# Sheet2.net
KiCad netlist of a schematic drawn in Altium Designer
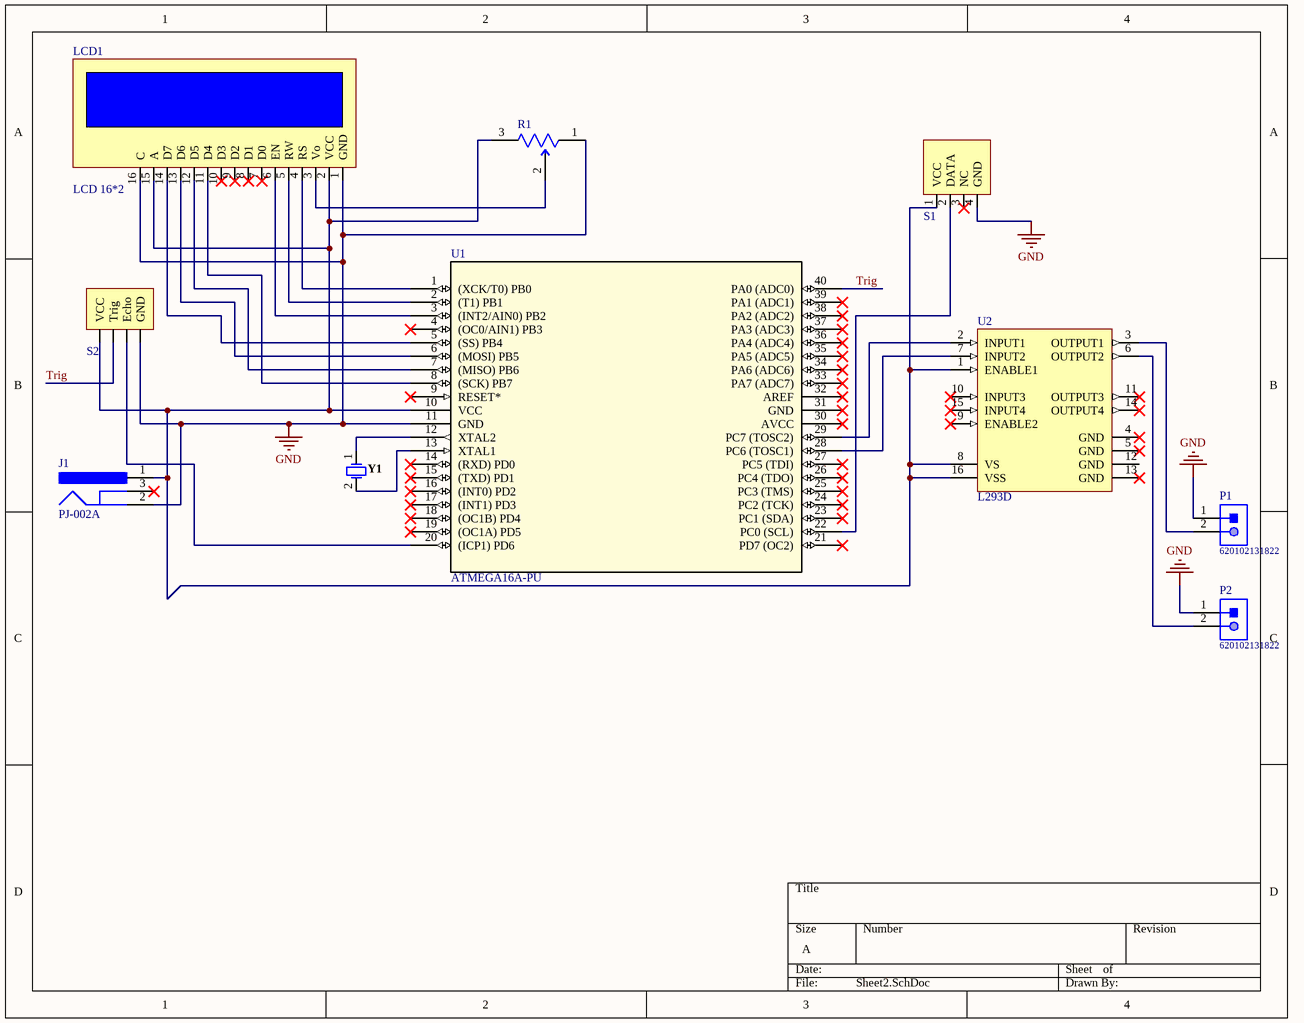
[diagram p0: Sheet2.SchDoc]

(export (version "E")
  (design (tool "Eeschema 10.0.6"))
  (components
    (comp (ref "J1")
      (value "PJ-002A")
      (footprint "CUI-PJ-002A_V")
      (fields (field (name "MANUFACTURER") "CUIInc.") (field (name "MANUFACTURER_1") "CUI"))
      (libsource (lib "AVRpr") (part "CMP-2000-06895-2"))
    )
    (comp (ref "LCD1") (value "LCD 16*2") (footprint "LCD1602") (libsource (lib "AVRpr") (part "LCD 16*2")))
    (comp (ref "P1")
      (value "620102131822")
      (footprint "620102131822")
      (description "Male Shrouded Header WR-WTB, SMT, Right Angled, pitch 2 mm, 1 x 2 position")
      (fields
        (field (name "MANUFACTURER") "Wurth Elektronik")
        (field (name "MANUFACTURER_1") "Wurth Electronics")
        (field (name "PUBLISHER") "WurthElektronik")
      )
      (libsource (lib "AVRpr") (part "CMP-1502-00669-1"))
    )
    (comp (ref "P2")
      (value "620102131822")
      (footprint "620102131822")
      (description "Male Shrouded Header WR-WTB, SMT, Right Angled, pitch 2 mm, 1 x 2 position")
      (fields
        (field (name "MANUFACTURER") "Wurth Elektronik")
        (field (name "MANUFACTURER_1") "Wurth Electronics")
        (field (name "PUBLISHER") "WurthElektronik")
      )
      (libsource (lib "AVRpr") (part "CMP-1502-00669-1"))
    )
    (comp (ref "R1")
      (value "3006P-1-103LF")
      (footprint "FP-3006P-MFG")
      (description "TRIMMER 10KOHM 0.75W PC PIN SIDE")
      (fields (field (name "TOLERANCE") "10%") (field (name "MANUFACTURER") "Bourns"))
      (libsource (lib "AVRpr") (part "CMP-07234-000047-1"))
    )
    (comp (ref "S1")
      (value "386")
      (footprint "DHT11")
      (description "SENSOR HUMID/TEMP 5V DTL 5% MOD")
      (fields (field (name "MANUFACTURER") "Adafruit Industries"))
      (libsource (lib "AVRpr") (part "386"))
    )
    (comp (ref "S2")
      (value "HC-SR04")
      (footprint "HC-SR04")
      (description "Ultrasonic Sensor Module, Rectangular, 20-4000 mm, 5 V, 15 mA, Arduino Compatible")
      (fields (field (name "MANUFACTURER") "OSEPP"))
      (libsource (lib "AVRpr") (part "HC-SR04"))
    )
    (comp (ref "U1")
      (value "ATMEGA16A-PU")
      (footprint "ATmega16A")
      (description "8-bit AVR MCU, 16 KB, 1024 Bytes, 16 MHz, 2.7 to 5.5V, PDIP-40, RoHS")
      (fields (field (name "MANUFACTURER") "Microchip / Atmel"))
      (libsource (lib "AVRpr") (part "ATMEGA16A-PU"))
    )
    (comp (ref "U2")
      (value "L293D")
      (footprint "STM-L293D-16")
      (description "Push-Pull Four Channel Driver with Diode, 4.5 to 36 V, -40 to 150 degC, 16-Pin PDIP, RoHS, Tube")
      (fields (field (name "MANUFACTURER") "STMicroelectronics"))
      (libsource (lib "AVRpr") (part "L293D"))
    )
    (comp (ref "Y1")
      (value "FOXSLF/080-20")
      (footprint "FOX-FOXSLF080-20")
      (description "Resistance Weld Thru-Hole Crystal, 8 MHz, -20 to 70 degC, 2-Pin THD, RoHS, Bulk")
      (fields (field (name "MANUFACTURER") "Fox Electronics"))
      (libsource (lib "AVRpr") (part "CMP-1749-00002-1"))
    )
  )
  (nets
    (net (code "1") (name "/Trig") (class "Default")
      (node (ref "S2") (pin "2") (pinfunction "Trig_2") (pintype "passive"))
      (node (ref "U1") (pin "40") (pinfunction "PA0_(ADC0)_40") (pintype "bidirectional"))
    )
    (net (code "2") (name "GND") (class "Default")
      (node (ref "J1") (pin "2") (pinfunction "2_2") (pintype "passive"))
      (node (ref "LCD1") (pin "1") (pinfunction "GND_1") (pintype "passive"))
      (node (ref "LCD1") (pin "16") (pinfunction "C_16") (pintype "passive"))
      (node (ref "P1") (pin "1") (pinfunction "1_1") (pintype "passive"))
      (node (ref "P2") (pin "1") (pinfunction "1_1") (pintype "passive"))
      (node (ref "R1") (pin "1") (pinfunction "CCW_1") (pintype "passive"))
      (node (ref "S1") (pin "4") (pinfunction "GND_4") (pintype "passive"))
      (node (ref "S2") (pin "4") (pinfunction "GND_4") (pintype "passive"))
      (node (ref "U1") (pin "11") (pinfunction "GND_11") (pintype "power_in"))
    )
    (net (code "3") (name "Net-(LCD1-A)") (class "Default")
      (node (ref "J1") (pin "1") (pinfunction "1_1") (pintype "passive"))
      (node (ref "LCD1") (pin "15") (pinfunction "A_15") (pintype "passive"))
      (node (ref "LCD1") (pin "2") (pinfunction "VCC_2") (pintype "passive"))
      (node (ref "R1") (pin "3") (pinfunction "CW_3") (pintype "passive"))
      (node (ref "S1") (pin "1") (pinfunction "VCC_1") (pintype "passive"))
      (node (ref "S2") (pin "1") (pinfunction "VCC_1") (pintype "passive"))
      (node (ref "U1") (pin "10") (pinfunction "VCC_10") (pintype "power_in"))
      (node (ref "U2") (pin "1") (pinfunction "ENABLE1_1") (pintype "input"))
      (node (ref "U2") (pin "16") (pinfunction "VSS_16") (pintype "power_in"))
      (node (ref "U2") (pin "8") (pinfunction "VS_8") (pintype "power_in"))
    )
    (net (code "4") (name "Net-(LCD1-D4)") (class "Default")
      (node (ref "LCD1") (pin "11") (pinfunction "D4_11") (pintype "passive"))
      (node (ref "U1") (pin "8") (pinfunction "(SCK)_PB7_8") (pintype "bidirectional"))
    )
    (net (code "5") (name "Net-(LCD1-D5)") (class "Default")
      (node (ref "LCD1") (pin "12") (pinfunction "D5_12") (pintype "passive"))
      (node (ref "U1") (pin "7") (pinfunction "(MISO)_PB6_7") (pintype "bidirectional"))
    )
    (net (code "6") (name "Net-(LCD1-D6)") (class "Default")
      (node (ref "LCD1") (pin "13") (pinfunction "D6_13") (pintype "passive"))
      (node (ref "U1") (pin "6") (pinfunction "(MOSI)_PB5_6") (pintype "bidirectional"))
    )
    (net (code "7") (name "Net-(LCD1-D7)") (class "Default")
      (node (ref "LCD1") (pin "14") (pinfunction "D7_14") (pintype "passive"))
      (node (ref "U1") (pin "5") (pinfunction "(SS)_PB4_5") (pintype "bidirectional"))
    )
    (net (code "8") (name "Net-(LCD1-EN)") (class "Default")
      (node (ref "LCD1") (pin "6") (pinfunction "EN_6") (pintype "passive"))
      (node (ref "U1") (pin "3") (pinfunction "(INT2/AIN0)_PB2_3") (pintype "bidirectional"))
    )
    (net (code "9") (name "Net-(LCD1-RS)") (class "Default")
      (node (ref "LCD1") (pin "4") (pinfunction "RS_4") (pintype "passive"))
      (node (ref "U1") (pin "1") (pinfunction "(XCK/T0)_PB0_1") (pintype "bidirectional"))
    )
    (net (code "10") (name "Net-(LCD1-RW)") (class "Default")
      (node (ref "LCD1") (pin "5") (pinfunction "RW_5") (pintype "passive"))
      (node (ref "U1") (pin "2") (pinfunction "(T1)_PB1_2") (pintype "bidirectional"))
    )
    (net (code "11") (name "Net-(LCD1-Vo)") (class "Default")
      (node (ref "LCD1") (pin "3") (pinfunction "Vo_3") (pintype "passive"))
      (node (ref "R1") (pin "2") (pinfunction "WIPER_2") (pintype "passive"))
    )
    (net (code "12") (name "Net-(S1-DATA)") (class "Default")
      (node (ref "S1") (pin "2") (pinfunction "DATA_2") (pintype "passive"))
      (node (ref "U1") (pin "22") (pinfunction "PC0_(SCL)_22") (pintype "bidirectional"))
    )
    (net (code "13") (name "Net-(S2-Echo)") (class "Default")
      (node (ref "S2") (pin "3") (pinfunction "Echo_3") (pintype "passive"))
      (node (ref "U1") (pin "20") (pinfunction "(ICP1)_PD6_20") (pintype "bidirectional"))
    )
    (net (code "14") (name "Net-(U1-PC6_(TOSC1))") (class "Default")
      (node (ref "U1") (pin "28") (pinfunction "PC6_(TOSC1)_28") (pintype "bidirectional"))
      (node (ref "U2") (pin "7") (pinfunction "INPUT2_7") (pintype "input"))
    )
    (net (code "15") (name "Net-(U1-PC7_(TOSC2))") (class "Default")
      (node (ref "U1") (pin "29") (pinfunction "PC7_(TOSC2)_29") (pintype "bidirectional"))
      (node (ref "U2") (pin "2") (pinfunction "INPUT1_2") (pintype "input"))
    )
    (net (code "16") (name "Net-(U1-XTAL1)") (class "Default")
      (node (ref "U1") (pin "13") (pinfunction "XTAL1_13") (pintype "input"))
      (node (ref "Y1") (pin "2") (pinfunction "2_2") (pintype "passive"))
    )
    (net (code "17") (name "Net-(U1-XTAL2)") (class "Default")
      (node (ref "U1") (pin "12") (pinfunction "XTAL2_12") (pintype "output"))
      (node (ref "Y1") (pin "1") (pinfunction "1_1") (pintype "passive"))
    )
    (net (code "18") (name "Net-(U2-OUTPUT1)") (class "Default")
      (node (ref "P1") (pin "2") (pinfunction "2_2") (pintype "passive"))
      (node (ref "U2") (pin "3") (pinfunction "OUTPUT1_3") (pintype "output"))
    )
    (net (code "19") (name "Net-(U2-OUTPUT2)") (class "Default")
      (node (ref "P2") (pin "2") (pinfunction "2_2") (pintype "passive"))
      (node (ref "U2") (pin "6") (pinfunction "OUTPUT2_6") (pintype "output"))
    )
    (net (code "20") (name "unconnected-(J1-Pad3)") (class "Default")
      (node (ref "J1") (pin "3") (pinfunction "3_3") (pintype "passive+no_connect"))
    )
    (net (code "21") (name "unconnected-(LCD1-D0-Pad7)") (class "Default")
      (node (ref "LCD1") (pin "7") (pinfunction "D0_7") (pintype "passive+no_connect"))
    )
    (net (code "22") (name "unconnected-(LCD1-D1-Pad8)") (class "Default")
      (node (ref "LCD1") (pin "8") (pinfunction "D1_8") (pintype "passive+no_connect"))
    )
    (net (code "23") (name "unconnected-(LCD1-D2-Pad9)") (class "Default")
      (node (ref "LCD1") (pin "9") (pinfunction "D2_9") (pintype "passive+no_connect"))
    )
    (net (code "24") (name "unconnected-(LCD1-D3-Pad10)") (class "Default")
      (node (ref "LCD1") (pin "10") (pinfunction "D3_10") (pintype "passive+no_connect"))
    )
    (net (code "25") (name "unconnected-(S1-NC-Pad3)") (class "Default")
      (node (ref "S1") (pin "3") (pinfunction "NC_3") (pintype "passive+no_connect"))
    )
    (net (code "26") (name "unconnected-(U1-(INT0)_PD2-Pad16)") (class "Default")
      (node (ref "U1") (pin "16") (pinfunction "(INT0)_PD2_16") (pintype "bidirectional+no_connect"))
    )
    (net (code "27") (name "unconnected-(U1-(INT1)_PD3-Pad17)") (class "Default")
      (node (ref "U1") (pin "17") (pinfunction "(INT1)_PD3_17") (pintype "bidirectional+no_connect"))
    )
    (net (code "28") (name "unconnected-(U1-(OC0{slash}AIN1)_PB3-Pad4)") (class "Default")
      (node (ref "U1") (pin "4") (pinfunction "(OC0/AIN1)_PB3_4") (pintype "bidirectional+no_connect"))
    )
    (net (code "29") (name "unconnected-(U1-(OC1A)_PD5-Pad19)") (class "Default")
      (node (ref "U1") (pin "19") (pinfunction "(OC1A)_PD5_19") (pintype "bidirectional+no_connect"))
    )
    (net (code "30") (name "unconnected-(U1-(OC1B)_PD4-Pad18)") (class "Default")
      (node (ref "U1") (pin "18") (pinfunction "(OC1B)_PD4_18") (pintype "bidirectional+no_connect"))
    )
    (net (code "31") (name "unconnected-(U1-(RXD)_PD0-Pad14)") (class "Default")
      (node (ref "U1") (pin "14") (pinfunction "(RXD)_PD0_14") (pintype "bidirectional+no_connect"))
    )
    (net (code "32") (name "unconnected-(U1-(TXD)_PD1-Pad15)") (class "Default")
      (node (ref "U1") (pin "15") (pinfunction "(TXD)_PD1_15") (pintype "bidirectional+no_connect"))
    )
    (net (code "33") (name "unconnected-(U1-AREF-Pad32)") (class "Default")
      (node (ref "U1") (pin "32") (pinfunction "AREF_32") (pintype "passive+no_connect"))
    )
    (net (code "34") (name "unconnected-(U1-AVCC-Pad30)") (class "Default")
      (node (ref "U1") (pin "30") (pinfunction "AVCC_30") (pintype "power_in+no_connect"))
    )
    (net (code "35") (name "unconnected-(U1-GND-Pad31)") (class "Default")
      (node (ref "U1") (pin "31") (pinfunction "GND_31") (pintype "power_in+no_connect"))
    )
    (net (code "36") (name "unconnected-(U1-PA1_(ADC1)-Pad39)") (class "Default")
      (node (ref "U1") (pin "39") (pinfunction "PA1_(ADC1)_39") (pintype "bidirectional+no_connect"))
    )
    (net (code "37") (name "unconnected-(U1-PA2_(ADC2)-Pad38)") (class "Default")
      (node (ref "U1") (pin "38") (pinfunction "PA2_(ADC2)_38") (pintype "bidirectional+no_connect"))
    )
    (net (code "38") (name "unconnected-(U1-PA3_(ADC3)-Pad37)") (class "Default")
      (node (ref "U1") (pin "37") (pinfunction "PA3_(ADC3)_37") (pintype "bidirectional+no_connect"))
    )
    (net (code "39") (name "unconnected-(U1-PA4_(ADC4)-Pad36)") (class "Default")
      (node (ref "U1") (pin "36") (pinfunction "PA4_(ADC4)_36") (pintype "bidirectional+no_connect"))
    )
    (net (code "40") (name "unconnected-(U1-PA5_(ADC5)-Pad35)") (class "Default")
      (node (ref "U1") (pin "35") (pinfunction "PA5_(ADC5)_35") (pintype "bidirectional+no_connect"))
    )
    (net (code "41") (name "unconnected-(U1-PA6_(ADC6)-Pad34)") (class "Default")
      (node (ref "U1") (pin "34") (pinfunction "PA6_(ADC6)_34") (pintype "bidirectional+no_connect"))
    )
    (net (code "42") (name "unconnected-(U1-PA7_(ADC7)-Pad33)") (class "Default")
      (node (ref "U1") (pin "33") (pinfunction "PA7_(ADC7)_33") (pintype "bidirectional+no_connect"))
    )
    (net (code "43") (name "unconnected-(U1-PC1_(SDA)-Pad23)") (class "Default")
      (node (ref "U1") (pin "23") (pinfunction "PC1_(SDA)_23") (pintype "bidirectional+no_connect"))
    )
    (net (code "44") (name "unconnected-(U1-PC2_(TCK)-Pad24)") (class "Default")
      (node (ref "U1") (pin "24") (pinfunction "PC2_(TCK)_24") (pintype "bidirectional+no_connect"))
    )
    (net (code "45") (name "unconnected-(U1-PC3_(TMS)-Pad25)") (class "Default")
      (node (ref "U1") (pin "25") (pinfunction "PC3_(TMS)_25") (pintype "bidirectional+no_connect"))
    )
    (net (code "46") (name "unconnected-(U1-PC4_(TDO)-Pad26)") (class "Default")
      (node (ref "U1") (pin "26") (pinfunction "PC4_(TDO)_26") (pintype "bidirectional+no_connect"))
    )
    (net (code "47") (name "unconnected-(U1-PC5_(TDI)-Pad27)") (class "Default")
      (node (ref "U1") (pin "27") (pinfunction "PC5_(TDI)_27") (pintype "bidirectional+no_connect"))
    )
    (net (code "48") (name "unconnected-(U1-PD7_(OC2)-Pad21)") (class "Default")
      (node (ref "U1") (pin "21") (pinfunction "PD7_(OC2)_21") (pintype "bidirectional+no_connect"))
    )
    (net (code "49") (name "unconnected-(U1-RESET*-Pad9)") (class "Default")
      (node (ref "U1") (pin "9") (pinfunction "RESET*_9") (pintype "input+no_connect"))
    )
    (net (code "50") (name "unconnected-(U2-ENABLE2-Pad9)") (class "Default")
      (node (ref "U2") (pin "9") (pinfunction "ENABLE2_9") (pintype "input+no_connect"))
    )
    (net (code "51") (name "unconnected-(U2-GND-Pad4)") (class "Default")
      (node (ref "U2") (pin "4") (pinfunction "GND_4") (pintype "power_in+no_connect"))
    )
    (net (code "52") (name "unconnected-(U2-GND-Pad5)") (class "Default")
      (node (ref "U2") (pin "5") (pinfunction "GND_5") (pintype "power_in+no_connect"))
    )
    (net (code "53") (name "unconnected-(U2-GND-Pad12)") (class "Default")
      (node (ref "U2") (pin "12") (pinfunction "GND_12") (pintype "power_in"))
    )
    (net (code "54") (name "unconnected-(U2-GND-Pad13)") (class "Default")
      (node (ref "U2") (pin "13") (pinfunction "GND_13") (pintype "power_in+no_connect"))
    )
    (net (code "55") (name "unconnected-(U2-INPUT3-Pad10)") (class "Default")
      (node (ref "U2") (pin "10") (pinfunction "INPUT3_10") (pintype "input+no_connect"))
    )
    (net (code "56") (name "unconnected-(U2-INPUT4-Pad15)") (class "Default")
      (node (ref "U2") (pin "15") (pinfunction "INPUT4_15") (pintype "input+no_connect"))
    )
    (net (code "57") (name "unconnected-(U2-OUTPUT3-Pad11)") (class "Default")
      (node (ref "U2") (pin "11") (pinfunction "OUTPUT3_11") (pintype "output+no_connect"))
    )
    (net (code "58") (name "unconnected-(U2-OUTPUT4-Pad14)") (class "Default")
      (node (ref "U2") (pin "14") (pinfunction "OUTPUT4_14") (pintype "output+no_connect"))
    )
  )
)
